# Four_Decade_BCD_Counter.net
KiCad netlist of a schematic drawn in Altium Designer
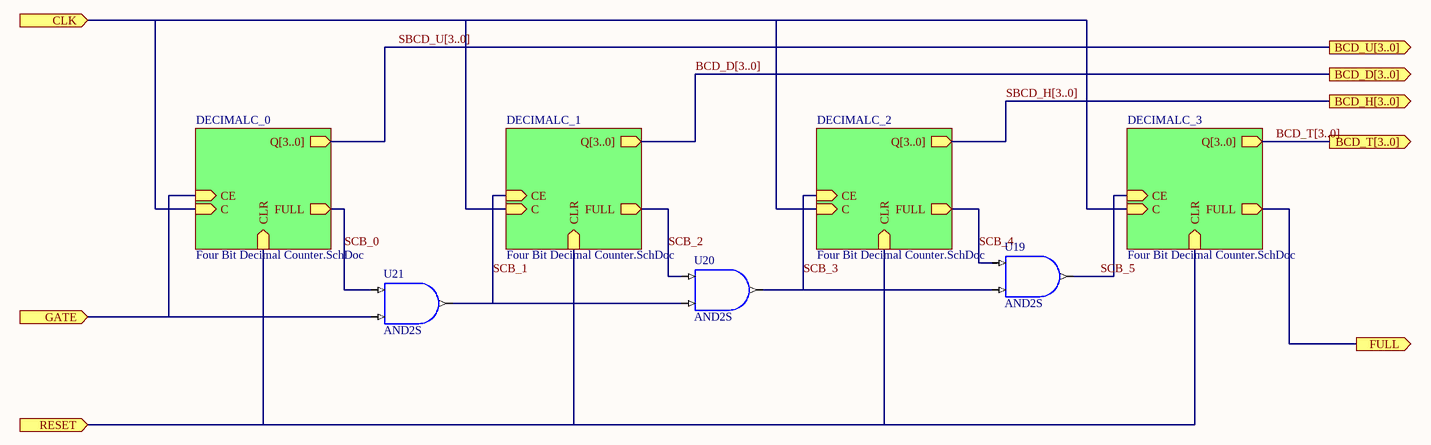
[diagram p0: Four Decade BCD Counter.SchDoc]

(export (version "E")
  (design (tool "Eeschema 10.0.6"))
  (components
    (comp (ref "U19")
      (value "AND2S")
      (description "2-Input AND Gate, Single Pin Version")
      (fields (field (name "PUBLISHER") "Altium Limited"))
      (libsource (lib "FPGA Generic") (part "AND2S"))
    )
    (comp (ref "U20")
      (value "AND2S")
      (description "2-Input AND Gate, Single Pin Version")
      (fields (field (name "PUBLISHER") "Altium Limited"))
      (libsource (lib "FPGA Generic") (part "AND2S"))
    )
    (comp (ref "U21")
      (value "AND2S")
      (description "2-Input AND Gate, Single Pin Version")
      (fields (field (name "PUBLISHER") "Altium Limited"))
      (libsource (lib "FPGA Generic") (part "AND2S"))
    )
  )
  (nets
    (net (code "27") (name "/GATE") (class "Default")
      (node (ref "U21") (pin "I1") (pinfunction "I1_I1") (pintype "input"))
    )
    (net (code "31") (name "/SCB_0") (class "Default")
      (node (ref "U21") (pin "I0") (pinfunction "I0_I0") (pintype "input"))
    )
    (net (code "33") (name "/SCB_2") (class "Default")
      (node (ref "U20") (pin "I0") (pinfunction "I0_I0") (pintype "input"))
    )
    (net (code "35") (name "/SCB_4") (class "Default")
      (node (ref "U19") (pin "I0") (pinfunction "I0_I0") (pintype "input"))
    )
    (net (code "36") (name "/SCB_5") (class "Default")
      (node (ref "U19") (pin "O") (pinfunction "O_O") (pintype "output"))
    )
    (net (code "37") (name "Net-(U19-PadI1)") (class "Default")
      (node (ref "U19") (pin "I1") (pinfunction "I1_I1") (pintype "input"))
      (node (ref "U20") (pin "O") (pinfunction "O_O") (pintype "output"))
    )
    (net (code "38") (name "Net-(U20-PadI1)") (class "Default")
      (node (ref "U20") (pin "I1") (pinfunction "I1_I1") (pintype "input"))
      (node (ref "U21") (pin "O") (pinfunction "O_O") (pintype "output"))
    )
  )
)
